# Communication_V1_1.net
KiCad netlist of a schematic drawn in Altium Designer
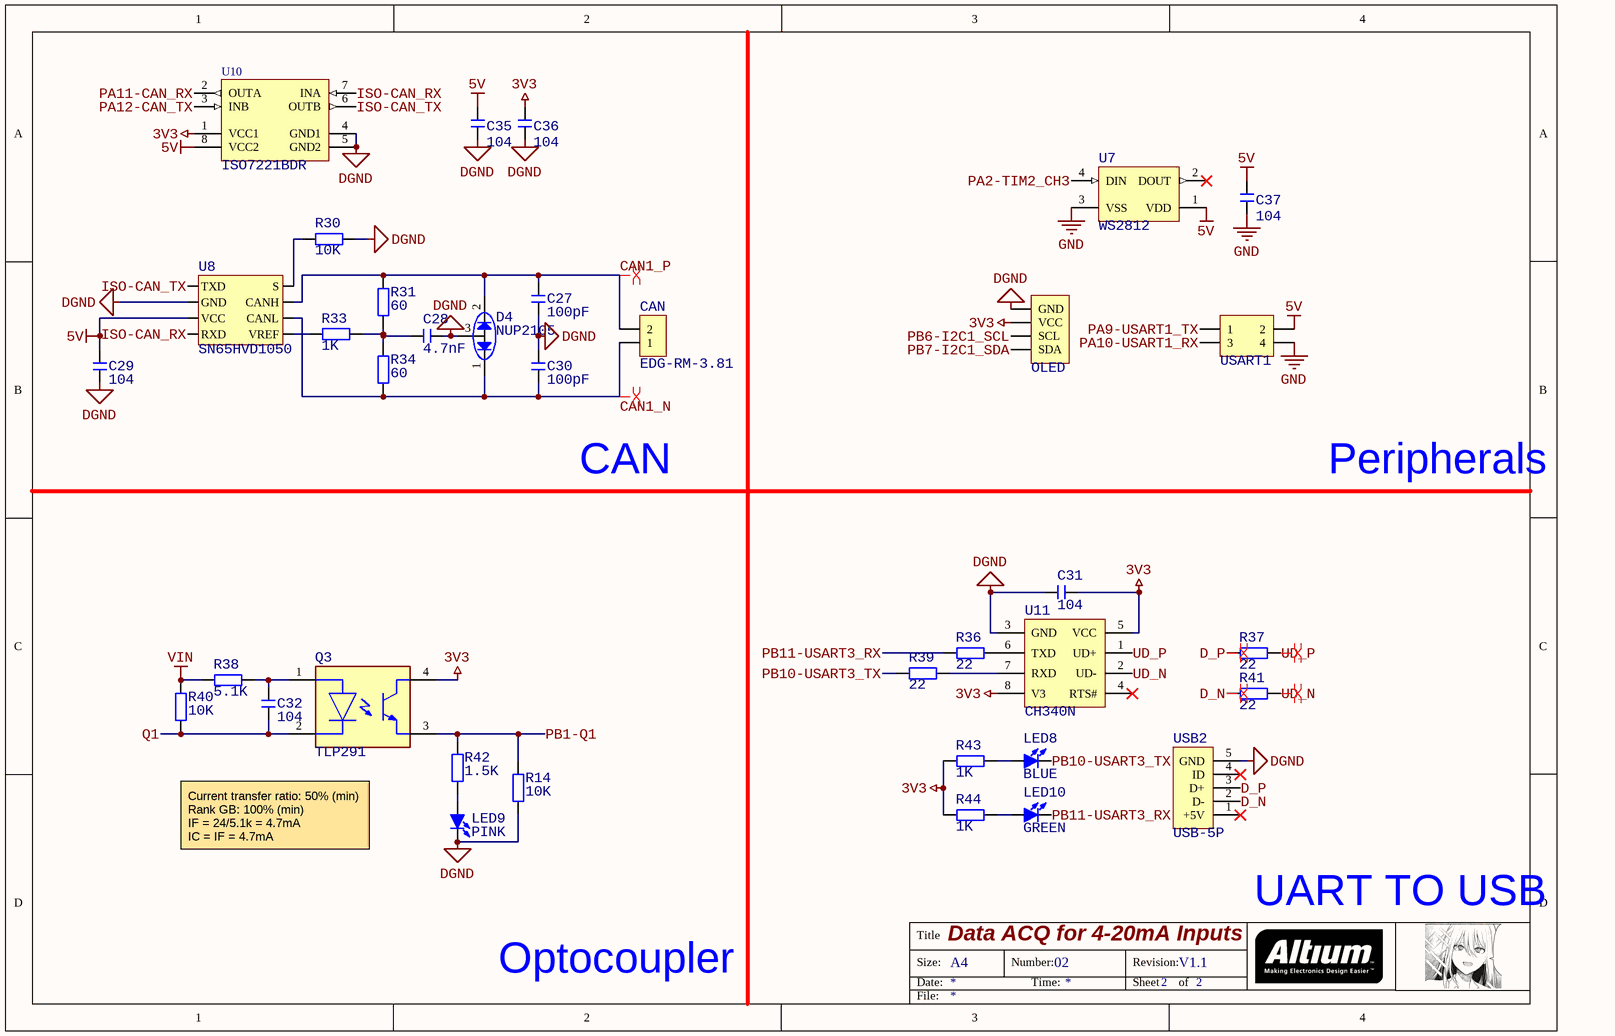
[diagram p0: Communication_V1.1.SchDoc]

(export (version "E")
  (design (tool "Eeschema 10.0.6"))
  (components
    (comp (ref "C27")
      (value "100pF")
      (footprint "C 0603_L")
      (description "无极性贴片电容")
      (libsource (lib "3.1   - 电阻-电容-电感") (part "C"))
    )
    (comp (ref "C28")
      (value "4.7nF")
      (footprint "C 0603_L")
      (description "无极性贴片电容")
      (libsource (lib "3.1   - 电阻-电容-电感") (part "C"))
    )
    (comp (ref "C29")
      (value "104")
      (footprint "C 0603_L")
      (description "无极性贴片电容")
      (libsource (lib "3.1   - 电阻-电容-电感") (part "C"))
    )
    (comp (ref "C30")
      (value "100pF")
      (footprint "C 0603_L")
      (description "无极性贴片电容")
      (libsource (lib "3.1   - 电阻-电容-电感") (part "C"))
    )
    (comp (ref "C31")
      (value "104")
      (footprint "C 0603_L")
      (description "无极性贴片电容")
      (libsource (lib "3.1   - 电阻-电容-电感") (part "C"))
    )
    (comp (ref "C32")
      (value "104")
      (footprint "C 0603_L")
      (description "无极性贴片电容")
      (libsource (lib "3.1   - 电阻-电容-电感") (part "C"))
    )
    (comp (ref "C35")
      (value "104")
      (footprint "C 0603_L")
      (description "无极性贴片电容")
      (libsource (lib "3.1   - 电阻-电容-电感") (part "C"))
    )
    (comp (ref "C36")
      (value "104")
      (footprint "C 0603_L")
      (description "无极性贴片电容")
      (libsource (lib "3.1   - 电阻-电容-电感") (part "C"))
    )
    (comp (ref "C37")
      (value "104")
      (footprint "C 0603_L")
      (description "无极性贴片电容")
      (libsource (lib "3.1   - 电阻-电容-电感") (part "C"))
    )
    (comp (ref "CAN")
      (value "EDG-RM-3.81")
      (footprint "15EDGRM-02P-3.81mm")
      (description "3.81间距")
      (libsource (lib "Elmo接插件") (part "绿头卧式2P"))
    )
    (comp (ref "D4")
      (value "NUP2105")
      (footprint "SOT23-3L")
      (description "表贴肖特基二极管")
      (libsource (lib "8.1   - 二极管-整流桥") (part "BAT54A"))
    )
    (comp (ref "LED8")
      (value "BLUE")
      (footprint "LED 0603B")
      (description "贴片LED")
      (libsource (lib "9.1   - LED") (part "LED-SMD"))
    )
    (comp (ref "LED9")
      (value "PINK")
      (footprint "LED 0603R")
      (description "贴片LED")
      (libsource (lib "9.1   - LED") (part "LED-SMD"))
    )
    (comp (ref "LED10")
      (value "GREEN")
      (footprint "LED 0603G")
      (description "贴片LED")
      (libsource (lib "9.1   - LED") (part "LED-SMD"))
    )
    (comp (ref "OLED")
      (value "HDR-1X4")
      (footprint "OLED_0.96寸-LI-4P")
      (description "OLED-4P接插件")
      (libsource (lib "KEY") (part "OLED_I2C_128*64"))
    )
    (comp (ref "Q3")
      (value "TLP291")
      (footprint "Everlight_EL3H7-G_MFG")
      (description "Optocoupler DC-IN 1-CH Transistor DC-OUT 4-Pin SSOP T/R")
      (libsource (lib "高级IC") (part "EL3H7_C_TA_-VG"))
    )
    (comp (ref "R14")
      (value "10K")
      (footprint "R 0603_L")
      (description "贴片电阻")
      (libsource (lib "3.1   - 电阻-电容-电感") (part "R"))
    )
    (comp (ref "R30")
      (value "10K")
      (footprint "R 0603_L")
      (description "贴片电阻")
      (libsource (lib "3.1   - 电阻-电容-电感") (part "R"))
    )
    (comp (ref "R31")
      (value "60")
      (footprint "R 0603_L")
      (description "贴片电阻")
      (libsource (lib "3.1   - 电阻-电容-电感") (part "R"))
    )
    (comp (ref "R33")
      (value "1K")
      (footprint "R 0603_L")
      (description "贴片电阻")
      (libsource (lib "3.1   - 电阻-电容-电感") (part "R"))
    )
    (comp (ref "R34")
      (value "60")
      (footprint "R 0603_L")
      (description "贴片电阻")
      (libsource (lib "3.1   - 电阻-电容-电感") (part "R"))
    )
    (comp (ref "R36")
      (value "22")
      (footprint "R 0603_L")
      (description "贴片电阻")
      (libsource (lib "3.1   - 电阻-电容-电感") (part "R"))
    )
    (comp (ref "R37")
      (value "22")
      (footprint "R 0603_L")
      (description "贴片电阻")
      (libsource (lib "3.1   - 电阻-电容-电感") (part "R"))
    )
    (comp (ref "R38")
      (value "5.1K")
      (footprint "R 0603_L")
      (description "贴片电阻")
      (libsource (lib "3.1   - 电阻-电容-电感") (part "R"))
    )
    (comp (ref "R39")
      (value "22")
      (footprint "R 0603_L")
      (description "贴片电阻")
      (libsource (lib "3.1   - 电阻-电容-电感") (part "R"))
    )
    (comp (ref "R40")
      (value "10K")
      (footprint "R 0603_L")
      (description "贴片电阻")
      (libsource (lib "3.1   - 电阻-电容-电感") (part "R"))
    )
    (comp (ref "R41")
      (value "22")
      (footprint "R 0603_L")
      (description "贴片电阻")
      (libsource (lib "3.1   - 电阻-电容-电感") (part "R"))
    )
    (comp (ref "R42")
      (value "1.5K")
      (footprint "R 0603_L")
      (description "贴片电阻")
      (libsource (lib "3.1   - 电阻-电容-电感") (part "R"))
    )
    (comp (ref "R43")
      (value "1K")
      (footprint "R 0603_L")
      (description "贴片电阻")
      (libsource (lib "3.1   - 电阻-电容-电感") (part "R"))
    )
    (comp (ref "R44")
      (value "1K")
      (footprint "R 0603_L")
      (description "贴片电阻")
      (libsource (lib "3.1   - 电阻-电容-电感") (part "R"))
    )
    (comp (ref "U7")
      (value "WS2812")
      (footprint "WS2812B_B")
      (fields (field (name "TOLERANCE") "10%") (field (name "PARTNUMBER") "WS2812B"))
      (libsource (lib "KEY") (part "WS2812"))
    )
    (comp (ref "U8")
      (value "SN65HVD1050")
      (footprint "SOP8_L")
      (description "EMC Optimized CAN Bus Transceiver")
      (libsource (lib "高级IC") (part "SN65HVD1050"))
    )
    (comp (ref "U10")
      (value "ISO7221BDR")
      (footprint "SOP8_L")
      (fields (field (name "MANUFACTURER") "Texas Instruments"))
      (libsource (lib "高级IC") (part "ISO7221BDR"))
    )
    (comp (ref "U11")
      (value "CH340N")
      (footprint "SOP8_N")
      (description "USB转串口芯片\r\nFull speed USB 2.0")
      (fields (field (name "PARTNUMBER") "TPS54232D") (field (name "MANUFACTURER") "Texas Instruments"))
      (libsource (lib "高级IC") (part "CH340N"))
    )
    (comp (ref "USART1")
      (value "Header2X2")
      (footprint "HDR2.54-M-LS-2x2P")
      (description "2*2P接插件")
      (libsource (lib "4.6   - 接插件-脚距2.54") (part "Header 2X2"))
    )
    (comp (ref "USB2")
      (value "USB-5P")
      (footprint "USB-MICRO_E")
      (description "微型USB母座")
      (libsource (lib "4.1   - 接口类") (part "USB-5P"))
    )
  )
  (nets
    (net (code "1") (name "/CAN1_N") (class "Default")
      (node (ref "C30") (pin "1") (pinfunction "1_1") (pintype "passive"))
      (node (ref "CAN") (pin "1") (pinfunction "1_1") (pintype "passive"))
      (node (ref "D4") (pin "1") (pinfunction "1_1") (pintype "passive"))
      (node (ref "R34") (pin "1") (pinfunction "1_1") (pintype "passive"))
      (node (ref "U8") (pin "6") (pinfunction "CANL_6") (pintype "passive"))
    )
    (net (code "2") (name "/CAN1_P") (class "Default")
      (node (ref "C27") (pin "2") (pinfunction "2_2") (pintype "passive"))
      (node (ref "CAN") (pin "2") (pinfunction "2_2") (pintype "passive"))
      (node (ref "D4") (pin "2") (pinfunction "2_2") (pintype "passive"))
      (node (ref "R31") (pin "2") (pinfunction "2_2") (pintype "passive"))
      (node (ref "U8") (pin "7") (pinfunction "CANH_7") (pintype "passive"))
    )
    (net (code "3") (name "/D_N") (class "Default")
      (node (ref "R41") (pin "1") (pinfunction "1_1") (pintype "passive"))
      (node (ref "USB2") (pin "2") (pinfunction "D-_2") (pintype "passive"))
    )
    (net (code "4") (name "/D_P") (class "Default")
      (node (ref "R37") (pin "1") (pinfunction "1_1") (pintype "passive"))
      (node (ref "USB2") (pin "3") (pinfunction "D+_3") (pintype "passive"))
    )
    (net (code "5") (name "/ISO-CAN_RX") (class "Default")
      (node (ref "U10") (pin "7") (pinfunction "INA_7") (pintype "input"))
      (node (ref "U8") (pin "4") (pinfunction "RXD_4") (pintype "passive"))
    )
    (net (code "6") (name "/ISO-CAN_TX") (class "Default")
      (node (ref "U10") (pin "6") (pinfunction "OUTB_6") (pintype "output"))
      (node (ref "U8") (pin "1") (pinfunction "TXD_1") (pintype "passive"))
    )
    (net (code "7") (name "/PA2-TIM2_CH3") (class "Default")
      (node (ref "U7") (pin "4") (pinfunction "DIN_4") (pintype "input"))
    )
    (net (code "8") (name "/PA9-USART1_TX") (class "Default")
      (node (ref "USART1") (pin "1") (pinfunction "1_1") (pintype "passive"))
    )
    (net (code "9") (name "/PA10-USART1_RX") (class "Default")
      (node (ref "USART1") (pin "3") (pinfunction "3_3") (pintype "passive"))
    )
    (net (code "10") (name "/PA11-CAN_RX") (class "Default")
      (node (ref "U10") (pin "2") (pinfunction "OUTA_2") (pintype "output"))
    )
    (net (code "11") (name "/PA12-CAN_TX") (class "Default")
      (node (ref "U10") (pin "3") (pinfunction "INB_3") (pintype "input"))
    )
    (net (code "12") (name "/PB1-Q1") (class "Default")
      (node (ref "Q3") (pin "3") (pinfunction "E_3") (pintype "passive"))
      (node (ref "R14") (pin "1") (pinfunction "1_1") (pintype "passive"))
      (node (ref "R42") (pin "1") (pinfunction "1_1") (pintype "passive"))
    )
    (net (code "13") (name "/PB6-I2C1_SCL") (class "Default")
      (node (ref "OLED") (pin "3") (pinfunction "SCL_3") (pintype "passive"))
    )
    (net (code "14") (name "/PB7-I2C1_SDA") (class "Default")
      (node (ref "OLED") (pin "4") (pinfunction "SDA_4") (pintype "passive"))
    )
    (net (code "15") (name "/PB10-USART3_TX") (class "Default")
      (node (ref "LED8") (pin "2") (pinfunction "K_2") (pintype "passive"))
      (node (ref "R39") (pin "1") (pinfunction "1_1") (pintype "passive"))
    )
    (net (code "16") (name "/PB11-USART3_RX") (class "Default")
      (node (ref "LED10") (pin "2") (pinfunction "K_2") (pintype "passive"))
      (node (ref "R36") (pin "1") (pinfunction "1_1") (pintype "passive"))
    )
    (net (code "17") (name "/Q1") (class "Default")
      (node (ref "C32") (pin "2") (pinfunction "2_2") (pintype "passive"))
      (node (ref "Q3") (pin "2") (pinfunction "C_2") (pintype "passive"))
      (node (ref "R40") (pin "2") (pinfunction "2_2") (pintype "passive"))
    )
    (net (code "18") (name "/UD_N") (class "Default")
      (node (ref "R41") (pin "2") (pinfunction "2_2") (pintype "passive"))
      (node (ref "U11") (pin "2") (pinfunction "UD-_2") (pintype "passive"))
    )
    (net (code "19") (name "/UD_P") (class "Default")
      (node (ref "R37") (pin "2") (pinfunction "2_2") (pintype "passive"))
      (node (ref "U11") (pin "1") (pinfunction "UD+_1") (pintype "passive"))
    )
    (net (code "20") (name "3V3") (class "Default")
      (node (ref "C31") (pin "1") (pinfunction "1_1") (pintype "passive"))
      (node (ref "C36") (pin "1") (pinfunction "1_1") (pintype "passive"))
      (node (ref "OLED") (pin "2") (pinfunction "VCC_2") (pintype "passive"))
      (node (ref "Q3") (pin "4") (pinfunction "C_4") (pintype "passive"))
      (node (ref "R43") (pin "1") (pinfunction "1_1") (pintype "passive"))
      (node (ref "R44") (pin "1") (pinfunction "1_1") (pintype "passive"))
      (node (ref "U10") (pin "1") (pinfunction "VCC1_1") (pintype "power_in"))
      (node (ref "U11") (pin "5") (pinfunction "VCC_5") (pintype "power_in"))
      (node (ref "U11") (pin "8") (pinfunction "V3_8") (pintype "passive"))
    )
    (net (code "21") (name "5V") (class "Default")
      (node (ref "C29") (pin "2") (pinfunction "2_2") (pintype "passive"))
      (node (ref "C35") (pin "1") (pinfunction "1_1") (pintype "passive"))
      (node (ref "C37") (pin "1") (pinfunction "1_1") (pintype "passive"))
      (node (ref "U10") (pin "8") (pinfunction "VCC2_8") (pintype "power_in"))
      (node (ref "U7") (pin "1") (pinfunction "VDD_1") (pintype "power_in"))
      (node (ref "U8") (pin "3") (pinfunction "VCC_3") (pintype "passive"))
      (node (ref "USART1") (pin "2") (pinfunction "2_2") (pintype "passive"))
    )
    (net (code "22") (name "DGND") (class "Default")
      (node (ref "C27") (pin "1") (pinfunction "1_1") (pintype "passive"))
      (node (ref "C28") (pin "2") (pinfunction "2_2") (pintype "passive"))
      (node (ref "C29") (pin "1") (pinfunction "1_1") (pintype "passive"))
      (node (ref "C30") (pin "2") (pinfunction "2_2") (pintype "passive"))
      (node (ref "C31") (pin "2") (pinfunction "2_2") (pintype "passive"))
      (node (ref "C35") (pin "2") (pinfunction "2_2") (pintype "passive"))
      (node (ref "C36") (pin "2") (pinfunction "2_2") (pintype "passive"))
      (node (ref "D4") (pin "3") (pinfunction "3_3") (pintype "passive"))
      (node (ref "LED9") (pin "2") (pinfunction "K_2") (pintype "passive"))
      (node (ref "OLED") (pin "1") (pinfunction "GND_1") (pintype "passive"))
      (node (ref "R14") (pin "2") (pinfunction "2_2") (pintype "passive"))
      (node (ref "R30") (pin "2") (pinfunction "2_2") (pintype "passive"))
      (node (ref "U10") (pin "4") (pinfunction "GND1_4") (pintype "power_in"))
      (node (ref "U10") (pin "5") (pinfunction "GND2_5") (pintype "power_in"))
      (node (ref "U11") (pin "3") (pinfunction "GND_3") (pintype "power_in"))
      (node (ref "U8") (pin "2") (pinfunction "GND_2") (pintype "passive"))
      (node (ref "USB2") (pin "5") (pinfunction "GND_5") (pintype "passive"))
    )
    (net (code "23") (name "GND") (class "Default")
      (node (ref "C37") (pin "2") (pinfunction "2_2") (pintype "passive"))
      (node (ref "U7") (pin "3") (pinfunction "VSS_3") (pintype "power_in"))
      (node (ref "USART1") (pin "4") (pinfunction "4_4") (pintype "passive"))
    )
    (net (code "24") (name "Net-(C28-Pad1)") (class "Default")
      (node (ref "C28") (pin "1") (pinfunction "1_1") (pintype "passive"))
      (node (ref "R31") (pin "1") (pinfunction "1_1") (pintype "passive"))
      (node (ref "R33") (pin "1") (pinfunction "1_1") (pintype "passive"))
      (node (ref "R34") (pin "2") (pinfunction "2_2") (pintype "passive"))
    )
    (net (code "25") (name "Net-(LED8-A)") (class "Default")
      (node (ref "LED8") (pin "1") (pinfunction "A_1") (pintype "passive"))
      (node (ref "R43") (pin "2") (pinfunction "2_2") (pintype "passive"))
    )
    (net (code "26") (name "Net-(LED9-A)") (class "Default")
      (node (ref "LED9") (pin "1") (pinfunction "A_1") (pintype "passive"))
      (node (ref "R42") (pin "2") (pinfunction "2_2") (pintype "passive"))
    )
    (net (code "27") (name "Net-(LED10-A)") (class "Default")
      (node (ref "LED10") (pin "1") (pinfunction "A_1") (pintype "passive"))
      (node (ref "R44") (pin "2") (pinfunction "2_2") (pintype "passive"))
    )
    (net (code "28") (name "Net-(Q3-A)") (class "Default")
      (node (ref "C32") (pin "1") (pinfunction "1_1") (pintype "passive"))
      (node (ref "Q3") (pin "1") (pinfunction "A_1") (pintype "passive"))
      (node (ref "R38") (pin "1") (pinfunction "1_1") (pintype "passive"))
    )
    (net (code "29") (name "Net-(U8-S)") (class "Default")
      (node (ref "R30") (pin "1") (pinfunction "1_1") (pintype "passive"))
      (node (ref "U8") (pin "8") (pinfunction "S_8") (pintype "passive"))
    )
    (net (code "30") (name "Net-(U8-VREF)") (class "Default")
      (node (ref "R33") (pin "2") (pinfunction "2_2") (pintype "passive"))
      (node (ref "U8") (pin "5") (pinfunction "VREF_5") (pintype "passive"))
    )
    (net (code "31") (name "Net-(U11-RXD)") (class "Default")
      (node (ref "R39") (pin "2") (pinfunction "2_2") (pintype "passive"))
      (node (ref "U11") (pin "7") (pinfunction "RXD_7") (pintype "passive"))
    )
    (net (code "32") (name "Net-(U11-TXD)") (class "Default")
      (node (ref "R36") (pin "2") (pinfunction "2_2") (pintype "passive"))
      (node (ref "U11") (pin "6") (pinfunction "TXD_6") (pintype "passive"))
    )
    (net (code "33") (name "VIN") (class "Default")
      (node (ref "R38") (pin "2") (pinfunction "2_2") (pintype "passive"))
      (node (ref "R40") (pin "1") (pinfunction "1_1") (pintype "passive"))
    )
    (net (code "34") (name "unconnected-(U7-DOUT-Pad2)") (class "Default")
      (node (ref "U7") (pin "2") (pinfunction "DOUT_2") (pintype "output+no_connect"))
    )
    (net (code "35") (name "unconnected-(U11-RTS#-Pad4)") (class "Default")
      (node (ref "U11") (pin "4") (pinfunction "RTS#_4") (pintype "power_in+no_connect"))
    )
    (net (code "36") (name "unconnected-(USB2-+5V-Pad1)") (class "Default")
      (node (ref "USB2") (pin "1") (pinfunction "+5V_1") (pintype "passive+no_connect"))
    )
    (net (code "37") (name "unconnected-(USB2-ID-Pad4)") (class "Default")
      (node (ref "USB2") (pin "4") (pinfunction "ID_4") (pintype "passive+no_connect"))
    )
  )
)
